# Analog.net
KiCad netlist of a schematic drawn in Altium Designer
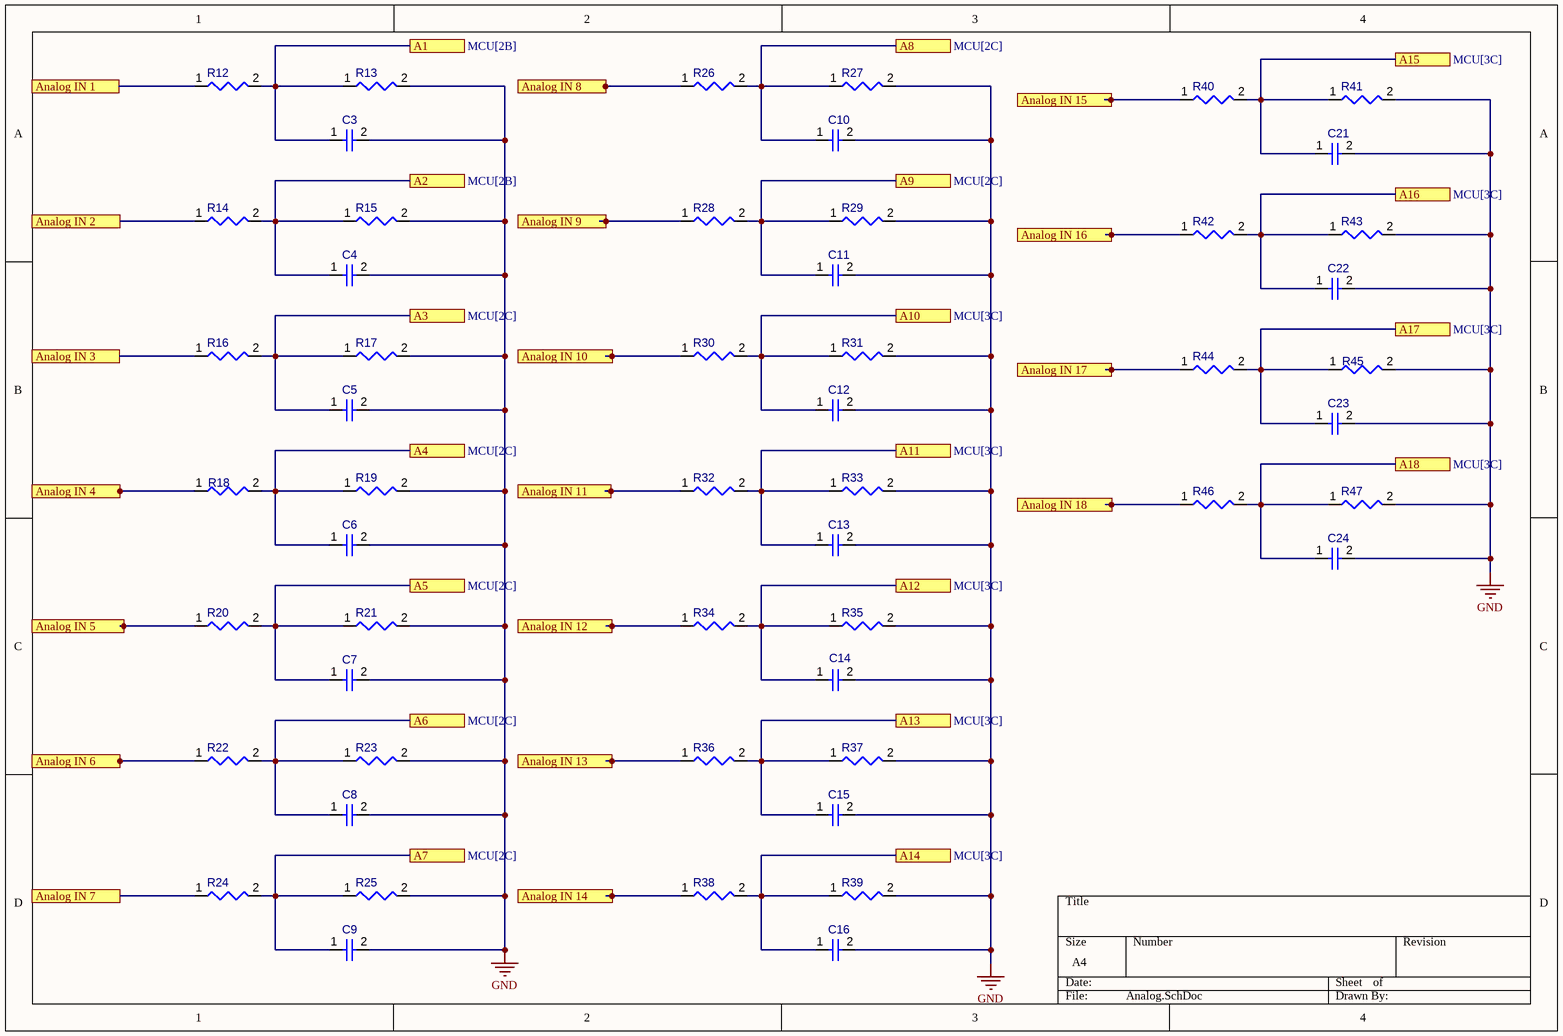
[diagram p0: Analog.SchDoc]

(export (version "E")
  (design (tool "Eeschema 10.0.6"))
  (components
    (comp (ref "C3")
      (value "AC0402KRX7R7BB333")
      (footprint "CAPC1005X04N")
      (description "33nF capacitor")
      (libsource (lib "Western Formula Racing") (part "CAP-NP-2"))
    )
    (comp (ref "C4")
      (value "AC0402KRX7R7BB333")
      (footprint "CAPC1005X04N")
      (description "33nF capacitor")
      (libsource (lib "Western Formula Racing") (part "CAP-NP-2"))
    )
    (comp (ref "C5")
      (value "AC0402KRX7R7BB333")
      (footprint "CAPC1005X04N")
      (description "33nF capacitor")
      (libsource (lib "Western Formula Racing") (part "CAP-NP-2"))
    )
    (comp (ref "C6")
      (value "AC0402KRX7R7BB333")
      (footprint "CAPC1005X04N")
      (description "33nF capacitor")
      (libsource (lib "Western Formula Racing") (part "CAP-NP-2"))
    )
    (comp (ref "C7")
      (value "AC0402KRX7R7BB333")
      (footprint "CAPC1005X04N")
      (description "33nF capacitor")
      (libsource (lib "Western Formula Racing") (part "CAP-NP-2"))
    )
    (comp (ref "C8")
      (value "AC0402KRX7R7BB333")
      (footprint "CAPC1005X04N")
      (description "33nF capacitor")
      (libsource (lib "Western Formula Racing") (part "CAP-NP-2"))
    )
    (comp (ref "C9")
      (value "AC0402KRX7R7BB333")
      (footprint "CAPC1005X04N")
      (description "33nF capacitor")
      (libsource (lib "Western Formula Racing") (part "CAP-NP-2"))
    )
    (comp (ref "C10")
      (value "AC0402KRX7R7BB333")
      (footprint "CAPC1005X04N")
      (description "33nF capacitor")
      (libsource (lib "Western Formula Racing") (part "CAP-NP-2"))
    )
    (comp (ref "C11")
      (value "AC0402KRX7R7BB333")
      (footprint "CAPC1005X04N")
      (description "33nF capacitor")
      (libsource (lib "Western Formula Racing") (part "CAP-NP-2"))
    )
    (comp (ref "C12")
      (value "AC0402KRX7R7BB333")
      (footprint "CAPC1005X04N")
      (description "33nF capacitor")
      (libsource (lib "Western Formula Racing") (part "CAP-NP-2"))
    )
    (comp (ref "C13")
      (value "AC0402KRX7R7BB333")
      (footprint "CAPC1005X04N")
      (description "33nF capacitor")
      (libsource (lib "Western Formula Racing") (part "CAP-NP-2"))
    )
    (comp (ref "C14")
      (value "AC0402KRX7R7BB333")
      (footprint "CAPC1005X04N")
      (description "33nF capacitor")
      (libsource (lib "Western Formula Racing") (part "CAP-NP-2"))
    )
    (comp (ref "C15")
      (value "AC0402KRX7R7BB333")
      (footprint "CAPC1005X04N")
      (description "33nF capacitor")
      (libsource (lib "Western Formula Racing") (part "CAP-NP-2"))
    )
    (comp (ref "C16")
      (value "AC0402KRX7R7BB333")
      (footprint "CAPC1005X04N")
      (description "33nF capacitor")
      (libsource (lib "Western Formula Racing") (part "CAP-NP-2"))
    )
    (comp (ref "C21")
      (value "AC0402KRX7R7BB333")
      (footprint "CAPC1005X04N")
      (description "33nF capacitor")
      (libsource (lib "Western Formula Racing") (part "CAP-NP-2"))
    )
    (comp (ref "C22")
      (value "AC0402KRX7R7BB333")
      (footprint "CAPC1005X04N")
      (description "33nF capacitor")
      (libsource (lib "Western Formula Racing") (part "CAP-NP-2"))
    )
    (comp (ref "C23")
      (value "AC0402KRX7R7BB333")
      (footprint "CAPC1005X04N")
      (description "33nF capacitor")
      (libsource (lib "Western Formula Racing") (part "CAP-NP-2"))
    )
    (comp (ref "C24")
      (value "AC0402KRX7R7BB333")
      (footprint "CAPC1005X04N")
      (description "33nF capacitor")
      (libsource (lib "Western Formula Racing") (part "CAP-NP-2"))
    )
    (comp (ref "R12")
      (value "0402WGD2002TCE")
      (footprint "CAPC1005X04N")
      (description "20k")
      (libsource (lib "Western Formula Racing") (part "RES-2"))
    )
    (comp (ref "R13")
      (value "SY0402DE30KP")
      (footprint "CAPC1005X04N")
      (description "30k Resistor")
      (libsource (lib "Western Formula Racing") (part "RES-2"))
    )
    (comp (ref "R14")
      (value "0402WGD2002TCE")
      (footprint "CAPC1005X04N")
      (description "20k")
      (libsource (lib "Western Formula Racing") (part "RES-2"))
    )
    (comp (ref "R15")
      (value "SY0402DE30KP")
      (footprint "CAPC1005X04N")
      (description "30k Resistor")
      (libsource (lib "Western Formula Racing") (part "RES-2"))
    )
    (comp (ref "R16")
      (value "0402WGD2002TCE")
      (footprint "CAPC1005X04N")
      (libsource (lib "Western Formula Racing") (part "RES-2"))
    )
    (comp (ref "R17")
      (value "SY0402DE30KP")
      (footprint "CAPC1005X04N")
      (description "30k Resistor")
      (libsource (lib "Western Formula Racing") (part "RES-2"))
    )
    (comp (ref "R18")
      (value "0402WGD2002TCE")
      (footprint "CAPC1005X04N")
      (libsource (lib "Western Formula Racing") (part "RES-2"))
    )
    (comp (ref "R19")
      (value "SY0402DE30KP")
      (footprint "CAPC1005X04N")
      (description "30k Resistor")
      (libsource (lib "Western Formula Racing") (part "RES-2"))
    )
    (comp (ref "R20")
      (value "0402WGD2002TCE")
      (footprint "CAPC1005X04N")
      (libsource (lib "Western Formula Racing") (part "RES-2"))
    )
    (comp (ref "R21")
      (value "SY0402DE30KP")
      (footprint "CAPC1005X04N")
      (description "30k Resistor")
      (libsource (lib "Western Formula Racing") (part "RES-2"))
    )
    (comp (ref "R22")
      (value "0402WGD2002TCE")
      (footprint "CAPC1005X04N")
      (libsource (lib "Western Formula Racing") (part "RES-2"))
    )
    (comp (ref "R23")
      (value "SY0402DE30KP")
      (footprint "CAPC1005X04N")
      (description "30k Resistor")
      (libsource (lib "Western Formula Racing") (part "RES-2"))
    )
    (comp (ref "R24")
      (value "0402WGD2002TCE")
      (footprint "CAPC1005X04N")
      (libsource (lib "Western Formula Racing") (part "RES-2"))
    )
    (comp (ref "R25")
      (value "SY0402DE30KP")
      (footprint "CAPC1005X04N")
      (description "30k Resistor")
      (libsource (lib "Western Formula Racing") (part "RES-2"))
    )
    (comp (ref "R26")
      (value "0402WGD2002TCE")
      (footprint "CAPC1005X04N")
      (libsource (lib "Western Formula Racing") (part "RES-2"))
    )
    (comp (ref "R27")
      (value "SY0402DE30KP")
      (footprint "CAPC1005X04N")
      (description "30k Resistor")
      (libsource (lib "Western Formula Racing") (part "RES-2"))
    )
    (comp (ref "R28")
      (value "0402WGD2002TCE")
      (footprint "CAPC1005X04N")
      (libsource (lib "Western Formula Racing") (part "RES-2"))
    )
    (comp (ref "R29")
      (value "SY0402DE30KP")
      (footprint "CAPC1005X04N")
      (description "30k Resistor")
      (libsource (lib "Western Formula Racing") (part "RES-2"))
    )
    (comp (ref "R30")
      (value "0402WGD2002TCE")
      (footprint "CAPC1005X04N")
      (libsource (lib "Western Formula Racing") (part "RES-2"))
    )
    (comp (ref "R31")
      (value "SY0402DE30KP")
      (footprint "CAPC1005X04N")
      (description "30k Resistor")
      (libsource (lib "Western Formula Racing") (part "RES-2"))
    )
    (comp (ref "R32")
      (value "0402WGD2002TCE")
      (footprint "CAPC1005X04N")
      (libsource (lib "Western Formula Racing") (part "RES-2"))
    )
    (comp (ref "R33")
      (value "SY0402DE30KP")
      (footprint "CAPC1005X04N")
      (description "30k Resistor")
      (libsource (lib "Western Formula Racing") (part "RES-2"))
    )
    (comp (ref "R34")
      (value "0402WGD2002TCE")
      (footprint "CAPC1005X04N")
      (libsource (lib "Western Formula Racing") (part "RES-2"))
    )
    (comp (ref "R35")
      (value "SY0402DE30KP")
      (footprint "CAPC1005X04N")
      (description "30k Resistor")
      (libsource (lib "Western Formula Racing") (part "RES-2"))
    )
    (comp (ref "R36")
      (value "0402WGD2002TCE")
      (footprint "CAPC1005X04N")
      (libsource (lib "Western Formula Racing") (part "RES-2"))
    )
    (comp (ref "R37")
      (value "SY0402DE30KP")
      (footprint "CAPC1005X04N")
      (description "30k Resistor")
      (libsource (lib "Western Formula Racing") (part "RES-2"))
    )
    (comp (ref "R38")
      (value "0402WGD2002TCE")
      (footprint "CAPC1005X04N")
      (libsource (lib "Western Formula Racing") (part "RES-2"))
    )
    (comp (ref "R39")
      (value "SY0402DE30KP")
      (footprint "CAPC1005X04N")
      (description "30k Resistor")
      (libsource (lib "Western Formula Racing") (part "RES-2"))
    )
    (comp (ref "R40")
      (value "0402WGD2002TCE")
      (footprint "CAPC1005X04N")
      (libsource (lib "Western Formula Racing") (part "RES-2"))
    )
    (comp (ref "R41")
      (value "SY0402DE30KP")
      (footprint "CAPC1005X04N")
      (description "30k Resistor")
      (libsource (lib "Western Formula Racing") (part "RES-2"))
    )
    (comp (ref "R42")
      (value "0402WGD2002TCE")
      (footprint "CAPC1005X04N")
      (libsource (lib "Western Formula Racing") (part "RES-2"))
    )
    (comp (ref "R43")
      (value "SY0402DE30KP")
      (footprint "CAPC1005X04N")
      (description "30k Resistor")
      (libsource (lib "Western Formula Racing") (part "RES-2"))
    )
    (comp (ref "R44")
      (value "0402WGD2002TCE")
      (footprint "CAPC1005X04N")
      (libsource (lib "Western Formula Racing") (part "RES-2"))
    )
    (comp (ref "R45")
      (value "SY0402DE30KP")
      (footprint "CAPC1005X04N")
      (description "30k Resistor")
      (libsource (lib "Western Formula Racing") (part "RES-2"))
    )
    (comp (ref "R46")
      (value "0402WGD2002TCE")
      (footprint "CAPC1005X04N")
      (libsource (lib "Western Formula Racing") (part "RES-2"))
    )
    (comp (ref "R47")
      (value "SY0402DE30KP")
      (footprint "CAPC1005X04N")
      (description "30k Resistor")
      (libsource (lib "Western Formula Racing") (part "RES-2"))
    )
  )
  (nets
    (net (code "1") (name "/A1") (class "Default")
      (node (ref "C3") (pin "1") (pinfunction "1_1") (pintype "passive"))
      (node (ref "R12") (pin "2") (pinfunction "2_2") (pintype "passive"))
      (node (ref "R13") (pin "1") (pinfunction "1_1") (pintype "passive"))
    )
    (net (code "2") (name "/A2") (class "Default")
      (node (ref "C4") (pin "1") (pinfunction "1_1") (pintype "passive"))
      (node (ref "R14") (pin "2") (pinfunction "2_2") (pintype "passive"))
      (node (ref "R15") (pin "1") (pinfunction "1_1") (pintype "passive"))
    )
    (net (code "3") (name "/A3") (class "Default")
      (node (ref "C5") (pin "1") (pinfunction "1_1") (pintype "passive"))
      (node (ref "R16") (pin "2") (pinfunction "2_2") (pintype "passive"))
      (node (ref "R17") (pin "1") (pinfunction "1_1") (pintype "passive"))
    )
    (net (code "4") (name "/A4") (class "Default")
      (node (ref "C6") (pin "1") (pinfunction "1_1") (pintype "passive"))
      (node (ref "R18") (pin "2") (pinfunction "2_2") (pintype "passive"))
      (node (ref "R19") (pin "1") (pinfunction "1_1") (pintype "passive"))
    )
    (net (code "5") (name "/A5") (class "Default")
      (node (ref "C7") (pin "1") (pinfunction "1_1") (pintype "passive"))
      (node (ref "R20") (pin "2") (pinfunction "2_2") (pintype "passive"))
      (node (ref "R21") (pin "1") (pinfunction "1_1") (pintype "passive"))
    )
    (net (code "6") (name "/A6") (class "Default")
      (node (ref "C8") (pin "1") (pinfunction "1_1") (pintype "passive"))
      (node (ref "R22") (pin "2") (pinfunction "2_2") (pintype "passive"))
      (node (ref "R23") (pin "1") (pinfunction "1_1") (pintype "passive"))
    )
    (net (code "7") (name "/A7") (class "Default")
      (node (ref "C9") (pin "1") (pinfunction "1_1") (pintype "passive"))
      (node (ref "R24") (pin "2") (pinfunction "2_2") (pintype "passive"))
      (node (ref "R25") (pin "1") (pinfunction "1_1") (pintype "passive"))
    )
    (net (code "8") (name "/A8") (class "Default")
      (node (ref "C10") (pin "1") (pinfunction "1_1") (pintype "passive"))
      (node (ref "R26") (pin "2") (pinfunction "2_2") (pintype "passive"))
      (node (ref "R27") (pin "1") (pinfunction "1_1") (pintype "passive"))
    )
    (net (code "9") (name "/A9") (class "Default")
      (node (ref "C11") (pin "1") (pinfunction "1_1") (pintype "passive"))
      (node (ref "R28") (pin "2") (pinfunction "2_2") (pintype "passive"))
      (node (ref "R29") (pin "1") (pinfunction "1_1") (pintype "passive"))
    )
    (net (code "10") (name "/A10") (class "Default")
      (node (ref "C12") (pin "1") (pinfunction "1_1") (pintype "passive"))
      (node (ref "R30") (pin "2") (pinfunction "2_2") (pintype "passive"))
      (node (ref "R31") (pin "1") (pinfunction "1_1") (pintype "passive"))
    )
    (net (code "11") (name "/A11") (class "Default")
      (node (ref "C13") (pin "1") (pinfunction "1_1") (pintype "passive"))
      (node (ref "R32") (pin "2") (pinfunction "2_2") (pintype "passive"))
      (node (ref "R33") (pin "1") (pinfunction "1_1") (pintype "passive"))
    )
    (net (code "12") (name "/A12") (class "Default")
      (node (ref "C14") (pin "1") (pinfunction "1_1") (pintype "passive"))
      (node (ref "R34") (pin "2") (pinfunction "2_2") (pintype "passive"))
      (node (ref "R35") (pin "1") (pinfunction "1_1") (pintype "passive"))
    )
    (net (code "13") (name "/A13") (class "Default")
      (node (ref "C15") (pin "1") (pinfunction "1_1") (pintype "passive"))
      (node (ref "R36") (pin "2") (pinfunction "2_2") (pintype "passive"))
      (node (ref "R37") (pin "1") (pinfunction "1_1") (pintype "passive"))
    )
    (net (code "14") (name "/A14") (class "Default")
      (node (ref "C16") (pin "1") (pinfunction "1_1") (pintype "passive"))
      (node (ref "R38") (pin "2") (pinfunction "2_2") (pintype "passive"))
      (node (ref "R39") (pin "1") (pinfunction "1_1") (pintype "passive"))
    )
    (net (code "15") (name "/A15") (class "Default")
      (node (ref "C21") (pin "1") (pinfunction "1_1") (pintype "passive"))
      (node (ref "R40") (pin "2") (pinfunction "2_2") (pintype "passive"))
      (node (ref "R41") (pin "1") (pinfunction "1_1") (pintype "passive"))
    )
    (net (code "16") (name "/A16") (class "Default")
      (node (ref "C22") (pin "1") (pinfunction "1_1") (pintype "passive"))
      (node (ref "R42") (pin "2") (pinfunction "2_2") (pintype "passive"))
      (node (ref "R43") (pin "1") (pinfunction "1_1") (pintype "passive"))
    )
    (net (code "17") (name "/A17") (class "Default")
      (node (ref "C23") (pin "1") (pinfunction "1_1") (pintype "passive"))
      (node (ref "R44") (pin "2") (pinfunction "2_2") (pintype "passive"))
      (node (ref "R45") (pin "1") (pinfunction "1_1") (pintype "passive"))
    )
    (net (code "18") (name "/A18") (class "Default")
      (node (ref "C24") (pin "1") (pinfunction "1_1") (pintype "passive"))
      (node (ref "R46") (pin "2") (pinfunction "2_2") (pintype "passive"))
      (node (ref "R47") (pin "1") (pinfunction "1_1") (pintype "passive"))
    )
    (net (code "19") (name "/Analog IN 1") (class "Default")
      (node (ref "R12") (pin "1") (pinfunction "1_1") (pintype "passive"))
    )
    (net (code "20") (name "/Analog IN 2") (class "Default")
      (node (ref "R14") (pin "1") (pinfunction "1_1") (pintype "passive"))
    )
    (net (code "21") (name "/Analog IN 3") (class "Default")
      (node (ref "R16") (pin "1") (pinfunction "1_1") (pintype "passive"))
    )
    (net (code "22") (name "/Analog IN 4") (class "Default")
      (node (ref "R18") (pin "1") (pinfunction "1_1") (pintype "passive"))
    )
    (net (code "23") (name "/Analog IN 5") (class "Default")
      (node (ref "R20") (pin "1") (pinfunction "1_1") (pintype "passive"))
    )
    (net (code "24") (name "/Analog IN 6") (class "Default")
      (node (ref "R22") (pin "1") (pinfunction "1_1") (pintype "passive"))
    )
    (net (code "25") (name "/Analog IN 7") (class "Default")
      (node (ref "R24") (pin "1") (pinfunction "1_1") (pintype "passive"))
    )
    (net (code "26") (name "/Analog IN 8") (class "Default")
      (node (ref "R26") (pin "1") (pinfunction "1_1") (pintype "passive"))
    )
    (net (code "27") (name "/Analog IN 9") (class "Default")
      (node (ref "R28") (pin "1") (pinfunction "1_1") (pintype "passive"))
    )
    (net (code "28") (name "/Analog IN 10") (class "Default")
      (node (ref "R30") (pin "1") (pinfunction "1_1") (pintype "passive"))
    )
    (net (code "29") (name "/Analog IN 11") (class "Default")
      (node (ref "R32") (pin "1") (pinfunction "1_1") (pintype "passive"))
    )
    (net (code "30") (name "/Analog IN 12") (class "Default")
      (node (ref "R34") (pin "1") (pinfunction "1_1") (pintype "passive"))
    )
    (net (code "31") (name "/Analog IN 13") (class "Default")
      (node (ref "R36") (pin "1") (pinfunction "1_1") (pintype "passive"))
    )
    (net (code "32") (name "/Analog IN 14") (class "Default")
      (node (ref "R38") (pin "1") (pinfunction "1_1") (pintype "passive"))
    )
    (net (code "33") (name "/Analog IN 15") (class "Default")
      (node (ref "R40") (pin "1") (pinfunction "1_1") (pintype "passive"))
    )
    (net (code "34") (name "/Analog IN 16") (class "Default")
      (node (ref "R42") (pin "1") (pinfunction "1_1") (pintype "passive"))
    )
    (net (code "35") (name "/Analog IN 17") (class "Default")
      (node (ref "R44") (pin "1") (pinfunction "1_1") (pintype "passive"))
    )
    (net (code "36") (name "/Analog IN 18") (class "Default")
      (node (ref "R46") (pin "1") (pinfunction "1_1") (pintype "passive"))
    )
    (net (code "37") (name "GND") (class "Default")
      (node (ref "C10") (pin "2") (pinfunction "2_2") (pintype "passive"))
      (node (ref "C11") (pin "2") (pinfunction "2_2") (pintype "passive"))
      (node (ref "C12") (pin "2") (pinfunction "2_2") (pintype "passive"))
      (node (ref "C13") (pin "2") (pinfunction "2_2") (pintype "passive"))
      (node (ref "C14") (pin "2") (pinfunction "2_2") (pintype "passive"))
      (node (ref "C15") (pin "2") (pinfunction "2_2") (pintype "passive"))
      (node (ref "C16") (pin "2") (pinfunction "2_2") (pintype "passive"))
      (node (ref "C21") (pin "2") (pinfunction "2_2") (pintype "passive"))
      (node (ref "C22") (pin "2") (pinfunction "2_2") (pintype "passive"))
      (node (ref "C23") (pin "2") (pinfunction "2_2") (pintype "passive"))
      (node (ref "C24") (pin "2") (pinfunction "2_2") (pintype "passive"))
      (node (ref "C3") (pin "2") (pinfunction "2_2") (pintype "passive"))
      (node (ref "C4") (pin "2") (pinfunction "2_2") (pintype "passive"))
      (node (ref "C5") (pin "2") (pinfunction "2_2") (pintype "passive"))
      (node (ref "C6") (pin "2") (pinfunction "2_2") (pintype "passive"))
      (node (ref "C7") (pin "2") (pinfunction "2_2") (pintype "passive"))
      (node (ref "C8") (pin "2") (pinfunction "2_2") (pintype "passive"))
      (node (ref "C9") (pin "2") (pinfunction "2_2") (pintype "passive"))
      (node (ref "R13") (pin "2") (pinfunction "2_2") (pintype "passive"))
      (node (ref "R15") (pin "2") (pinfunction "2_2") (pintype "passive"))
      (node (ref "R17") (pin "2") (pinfunction "2_2") (pintype "passive"))
      (node (ref "R19") (pin "2") (pinfunction "2_2") (pintype "passive"))
      (node (ref "R21") (pin "2") (pinfunction "2_2") (pintype "passive"))
      (node (ref "R23") (pin "2") (pinfunction "2_2") (pintype "passive"))
      (node (ref "R25") (pin "2") (pinfunction "2_2") (pintype "passive"))
      (node (ref "R27") (pin "2") (pinfunction "2_2") (pintype "passive"))
      (node (ref "R29") (pin "2") (pinfunction "2_2") (pintype "passive"))
      (node (ref "R31") (pin "2") (pinfunction "2_2") (pintype "passive"))
      (node (ref "R33") (pin "2") (pinfunction "2_2") (pintype "passive"))
      (node (ref "R35") (pin "2") (pinfunction "2_2") (pintype "passive"))
      (node (ref "R37") (pin "2") (pinfunction "2_2") (pintype "passive"))
      (node (ref "R39") (pin "2") (pinfunction "2_2") (pintype "passive"))
      (node (ref "R41") (pin "2") (pinfunction "2_2") (pintype "passive"))
      (node (ref "R43") (pin "2") (pinfunction "2_2") (pintype "passive"))
      (node (ref "R45") (pin "2") (pinfunction "2_2") (pintype "passive"))
      (node (ref "R47") (pin "2") (pinfunction "2_2") (pintype "passive"))
    )
  )
)
